# fillcap_rect.net
KiCad netlist of a schematic drawn in Altium Designer
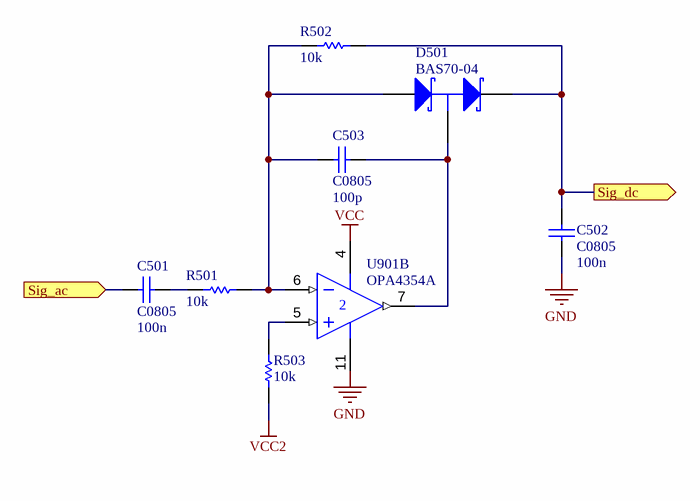
[diagram p0: fillcap_rect.SchDoc]

(export (version "E")
  (design (tool "Eeschema 10.0.6"))
  (components
    (comp (ref "C501")
      (value "C0805")
      (footprint "0805")
      (description "Ceramic Chip Capacitor - Standard")
      (fields (field (name "ALTIUM_VALUE") "100n") (field (name "PUBLISHER") "Altium Limited"))
      (libsource (lib "KEMET Chip Capacitor") (part "C0805"))
    )
    (comp (ref "C502")
      (value "C0805")
      (footprint "0805")
      (description "Ceramic Chip Capacitor - Standard")
      (fields (field (name "ALTIUM_VALUE") "100n") (field (name "PUBLISHER") "Altium Limited"))
      (libsource (lib "KEMET Chip Capacitor") (part "C0805"))
    )
    (comp (ref "C503")
      (value "C0805")
      (footprint "0805")
      (description "Ceramic Chip Capacitor - Standard")
      (fields (field (name "ALTIUM_VALUE") "100p") (field (name "PUBLISHER") "Altium Limited"))
      (libsource (lib "KEMET Chip Capacitor") (part "C0805"))
    )
    (comp (ref "D501")
      (value "BAS70-04")
      (footprint "SOT23_N")
      (description "Schottky Barrier Double Diode")
      (fields (field (name "PUBLISHER") "Altium Limited"))
      (libsource (lib "Philips Discrete Diode - Schottky") (part "BAS70-04"))
    )
    (comp (ref "R501")
      (value "10k")
      (footprint "ERA-0805")
      (fields (field (name "PUBLISHER") "Altium Limited"))
      (libsource (lib "Panasonic Resistor") (part "ERAS"))
    )
    (comp (ref "R502")
      (value "10k")
      (footprint "ERA-0805")
      (fields (field (name "PUBLISHER") "Altium Limited"))
      (libsource (lib "Panasonic Resistor") (part "ERAS"))
    )
    (comp (ref "R503")
      (value "10k")
      (footprint "ERA-0805")
      (fields (field (name "PUBLISHER") "Altium Limited"))
      (libsource (lib "Panasonic Resistor") (part "ERAS"))
    )
    (comp (ref "U901")
      (value "OPA4354A")
      (footprint "D014_N")
      (description "Quadruple Operational Amplifier")
      (fields (field (name "PUBLISHER") "Altium Limited"))
      (libsource (lib "TI Operational Amplifier") (part "LM324AD"))
    )
  )
  (nets
    (net (code "1") (name "/Sig_ac") (class "Default")
      (node (ref "C501") (pin "2") (pinfunction "2_2") (pintype "passive"))
    )
    (net (code "2") (name "/Sig_dc") (class "Default")
      (node (ref "C502") (pin "1") (pinfunction "1_1") (pintype "passive"))
      (node (ref "D501") (pin "2") (pinfunction "K_2") (pintype "passive"))
      (node (ref "R502") (pin "2") (pinfunction "2_2") (pintype "passive"))
    )
    (net (code "3") (name "GND") (class "Default")
      (node (ref "C502") (pin "2") (pinfunction "2_2") (pintype "passive"))
      (node (ref "U901") (pin "11") (pinfunction "V-_11") (pintype "power_in"))
    )
    (net (code "4") (name "Net-(C501-Pad1)") (class "Default")
      (node (ref "C501") (pin "1") (pinfunction "1_1") (pintype "passive"))
      (node (ref "R501") (pin "1") (pinfunction "1_1") (pintype "passive"))
    )
    (net (code "5") (name "Net-(D501-A)") (class "Default")
      (node (ref "C503") (pin "2") (pinfunction "2_2") (pintype "passive"))
      (node (ref "D501") (pin "1") (pinfunction "A_1") (pintype "passive"))
      (node (ref "R501") (pin "2") (pinfunction "2_2") (pintype "passive"))
      (node (ref "R502") (pin "1") (pinfunction "1_1") (pintype "passive"))
      (node (ref "U901") (pin "6") (pinfunction "IN-_6") (pintype "input"))
    )
    (net (code "6") (name "Net-(D501-C)") (class "Default")
      (node (ref "C503") (pin "1") (pinfunction "1_1") (pintype "passive"))
      (node (ref "D501") (pin "3") (pinfunction "C_3") (pintype "passive"))
      (node (ref "U901") (pin "7") (pinfunction "OUT_7") (pintype "output"))
    )
    (net (code "7") (name "Net-(U901B-IN+)") (class "Default")
      (node (ref "R503") (pin "2") (pinfunction "2_2") (pintype "passive"))
      (node (ref "U901") (pin "5") (pinfunction "IN+_5") (pintype "input"))
    )
    (net (code "8") (name "VCC") (class "Default")
      (node (ref "U901") (pin "4") (pinfunction "V+_4") (pintype "power_in"))
    )
    (net (code "9") (name "VCC2") (class "Default")
      (node (ref "R503") (pin "1") (pinfunction "1_1") (pintype "passive"))
    )
  )
)
